# MySens-easyESP32-012.net
KiCad netlist of a schematic drawn in EAGLE
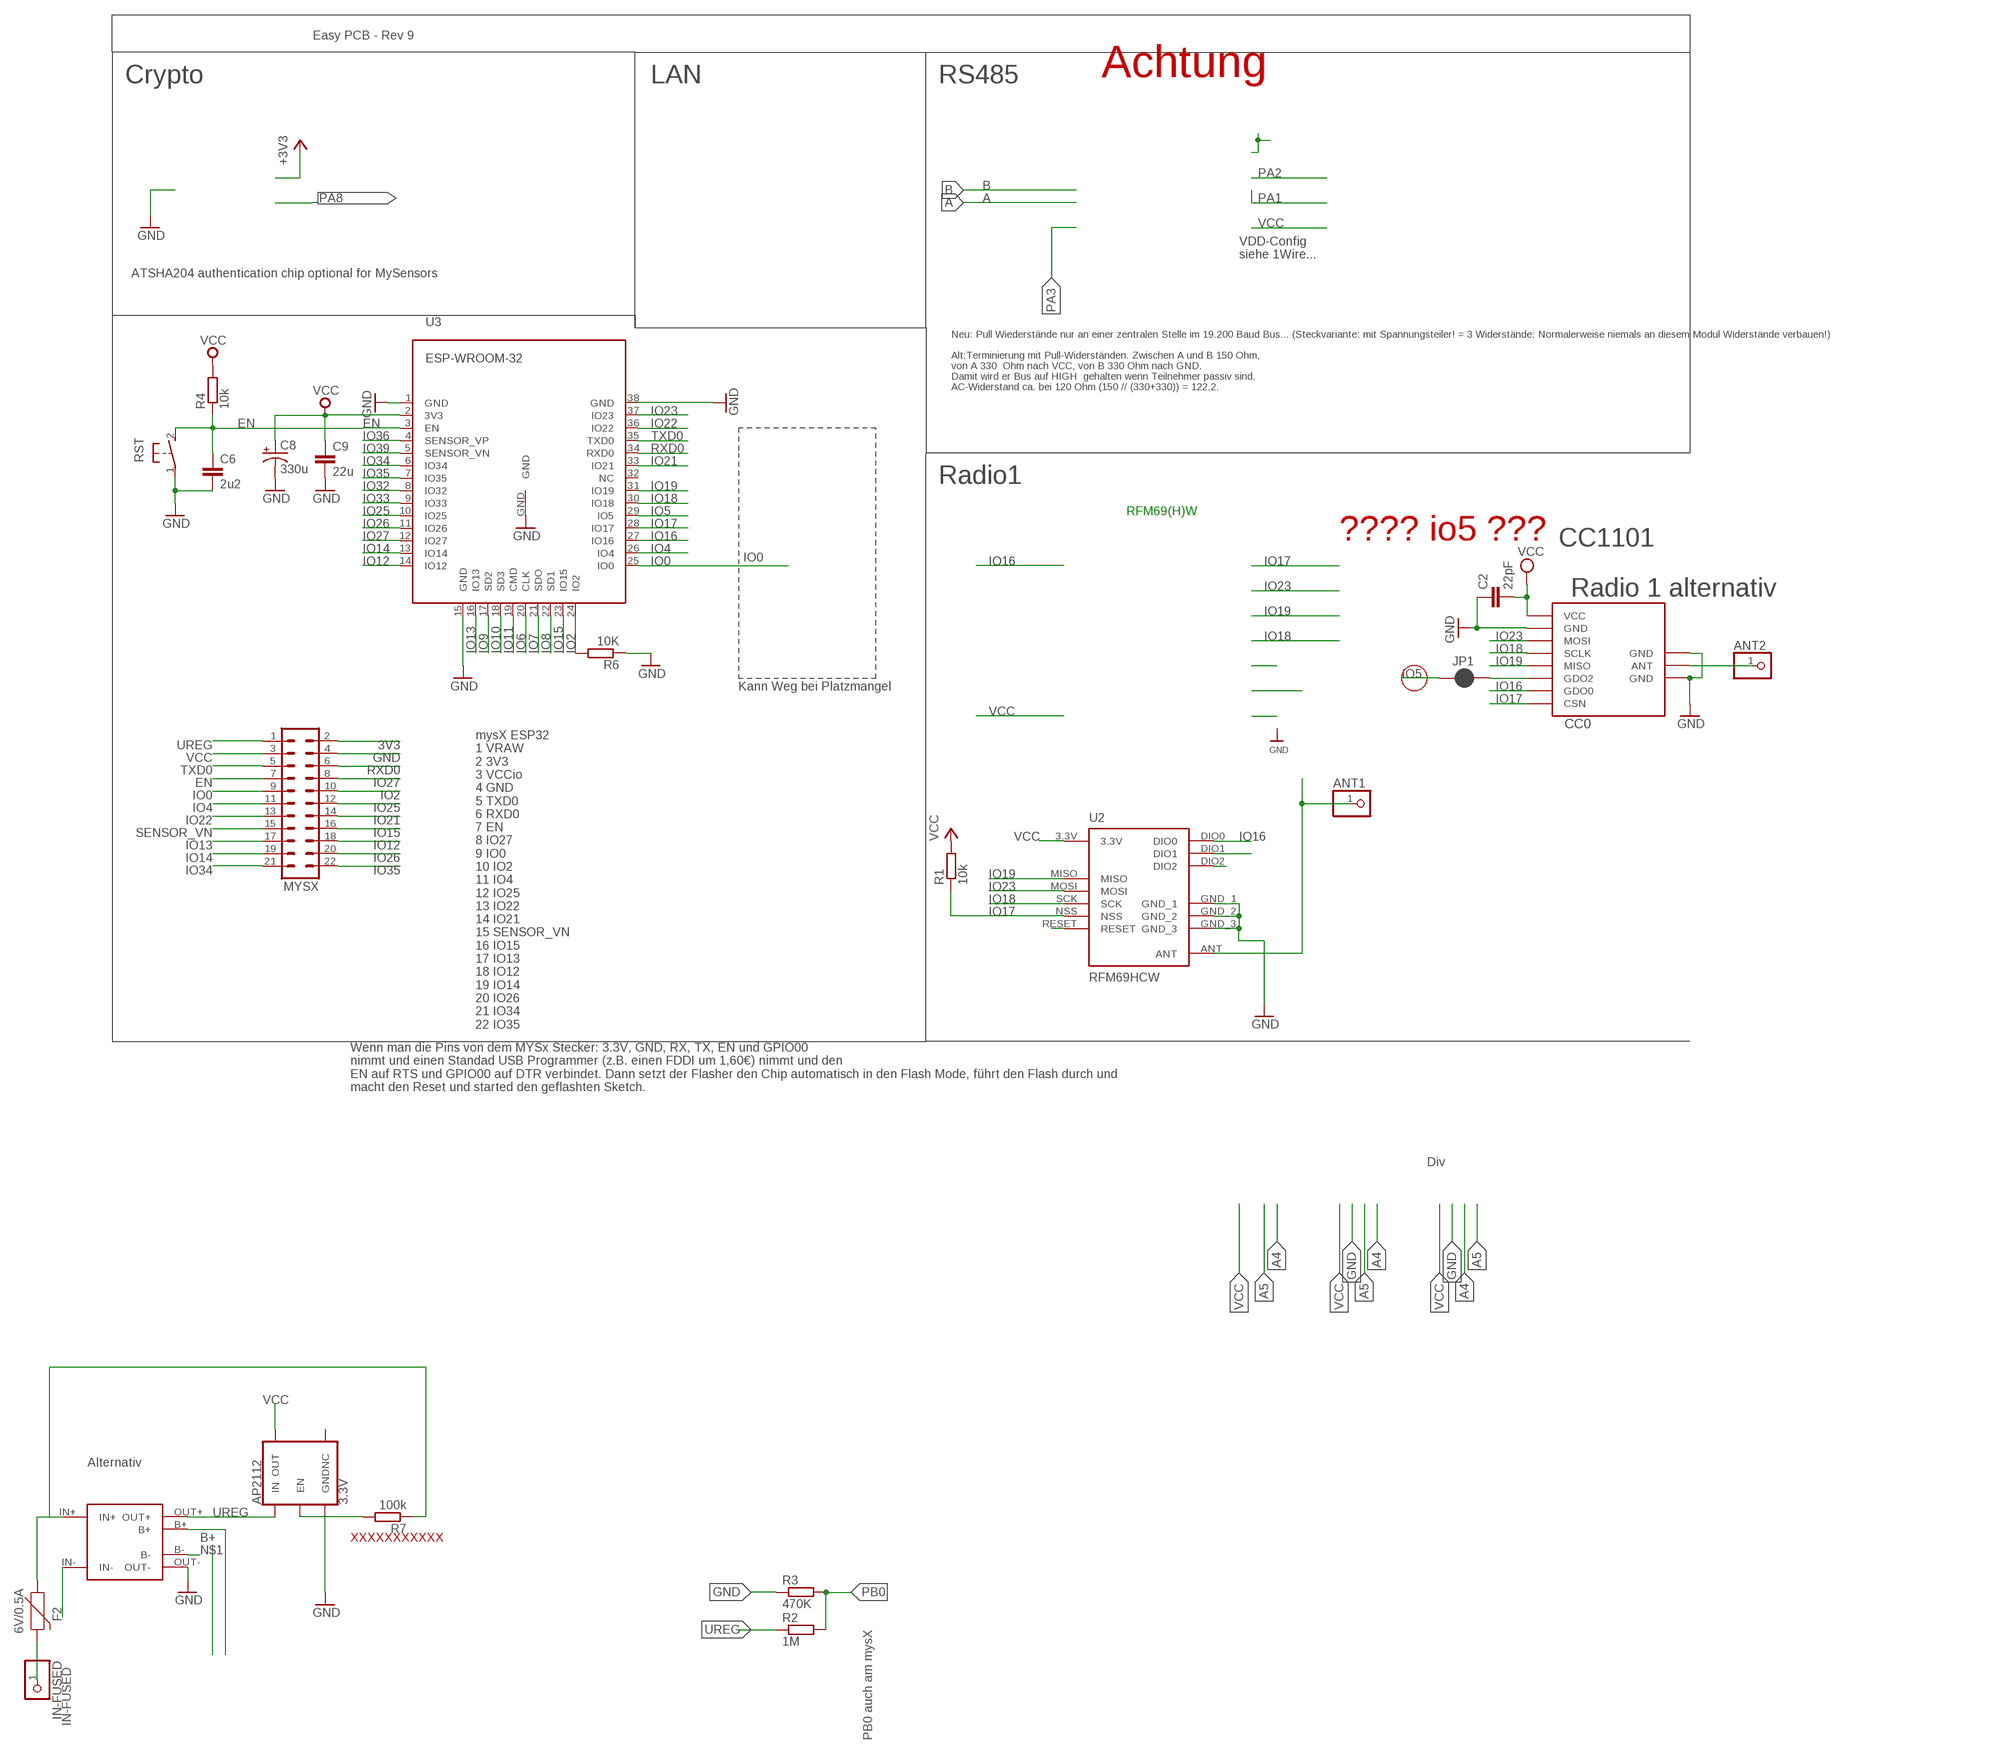
[diagram p0: schematic, sheet 1]

(export (version "E")
  (design (tool "Eeschema 10.0.6"))
  (components
    (comp (ref "ANT1")
      (value "PINHD-1X1")
      (footprint "eagle-import:1X01")
      (libsource (lib "eagle-import") (part "PINHD-1X1"))
    )
    (comp (ref "ANT2")
      (value "PINHD-1X1")
      (footprint "eagle-import:1X01")
      (libsource (lib "eagle-import") (part "PINHD-1X1"))
    )
    (comp (ref "AP2112")
      (value "3.3V")
      (footprint "eagle-import:SOT23-5")
      (libsource (lib "eagle-import") (part "V_REG_AP2112K-3.3V"))
    )
    (comp (ref "C2")
      (value "22pF")
      (footprint "eagle-import:C0805")
      (libsource (lib "eagle-import") (part "C-EUC0805"))
    )
    (comp (ref "C6")
      (value "2u2")
      (footprint "eagle-import:C0805")
      (libsource (lib "eagle-import") (part "rcl@1_C-EUC0805"))
    )
    (comp (ref "C8")
      (value "330u")
      (footprint "eagle-import:VISHAY_C")
      (libsource (lib "eagle-import") (part "CAP_POLSMD"))
    )
    (comp (ref "C9")
      (value "22u")
      (footprint "eagle-import:C0805")
      (libsource (lib "eagle-import") (part "rcl@1_C-EUC0805"))
    )
    (comp (ref "CC0")
      (value "CC1101")
      (footprint "eagle-import:CC1101_MODULE1_SMD")
      (libsource (lib "eagle-import") (part "CC1101_MODULE1SMD"))
    )
    (comp (ref "F2")
      (value "6V/0.5A")
      (footprint "eagle-import:1206")
      (libsource (lib "eagle-import") (part "PPTC_HALF-AMP"))
    )
    (comp (ref "IN-FUSED")
      (value "PINHD-1X1")
      (footprint "eagle-import:1X01")
      (libsource (lib "eagle-import") (part "PINHD-1X1"))
    )
    (comp (ref "JP1")
      (value "JUMPER-SMT_2_NC_PASTE_NO-SILK")
      (footprint "eagle-import:SMT-JUMPER_2_NC_PASTE_NO-SILK")
      (libsource (lib "eagle-import") (part "JUMPER-SMT_2_NC_PASTE_NO-SILK"))
    )
    (comp (ref "MYSX")
      (value "MA11-2")
      (footprint "eagle-import:MA11-2")
      (libsource (lib "eagle-import") (part "MA11-2"))
    )
    (comp (ref "R1")
      (value "10k")
      (footprint "eagle-import:M0805")
      (libsource (lib "eagle-import") (part "R-EU_M0805"))
    )
    (comp (ref "R2")
      (value "1M")
      (footprint "eagle-import:M0805")
      (libsource (lib "eagle-import") (part "R-EU_M0805"))
    )
    (comp (ref "R3")
      (value "470K")
      (footprint "eagle-import:M0805")
      (libsource (lib "eagle-import") (part "R-EU_M0805"))
    )
    (comp (ref "R4")
      (value "10k")
      (footprint "eagle-import:M0805")
      (libsource (lib "eagle-import") (part "rcl@1_R-EU_M0805"))
    )
    (comp (ref "R6")
      (value "10K")
      (footprint "eagle-import:M0805")
      (libsource (lib "eagle-import") (part "R-EU_M0805"))
    )
    (comp (ref "R7")
      (value "100k")
      (footprint "eagle-import:M0805")
      (libsource (lib "eagle-import") (part "R-EU_M0805"))
    )
    (comp (ref "RST")
      (value "DTSM-3")
      (footprint "eagle-import:DTSM-3")
      (libsource (lib "eagle-import") (part "DTSM-3"))
    )
    (comp (ref "TP4056")
      (value "TP4056-MODULE")
      (footprint "eagle-import:TP4056-LITHIUM-PROTECTED-MODULE")
      (libsource (lib "eagle-import") (part "TP4056-MODULE"))
    )
    (comp (ref "U2")
      (value "RFM69HCW")
      (footprint "eagle-import:RFM69HCW-XXXS2")
      (libsource (lib "eagle-import") (part "RFM69HCW"))
    )
    (comp (ref "U3")
      (value "ESP-WROOM-32")
      (footprint "eagle-import:ESP-WROOM-32")
      (libsource (lib "eagle-import") (part "ESP-WROOM-32"))
    )
  )
  (nets
    (net (code "2") (name "/3V3") (class "Default")
      (node (ref "MYSX") (pin "2") (pinfunction "2_2") (pintype "passive"))
    )
    (net (code "3") (name "/B+") (class "Default")
      (node (ref "TP4056") (pin "B+") (pinfunction "B+_B+") (pintype "power_in"))
    )
    (net (code "4") (name "/EN") (class "Default")
      (node (ref "C6") (pin "1") (pinfunction "1_1") (pintype "passive"))
      (node (ref "MYSX") (pin "7") (pinfunction "7_7") (pintype "passive"))
      (node (ref "R4") (pin "1") (pinfunction "1_1") (pintype "passive"))
      (node (ref "RST") (pin "2") (pinfunction "2_2") (pintype "passive"))
      (node (ref "U3") (pin "3") (pinfunction "EN_3") (pintype "bidirectional"))
    )
    (net (code "5") (name "/IN-FUSED") (class "Default")
      (node (ref "F2") (pin "2") (pinfunction "2_2") (pintype "bidirectional"))
      (node (ref "IN-FUSED") (pin "1") (pinfunction "1_1") (pintype "passive"))
    )
    (net (code "6") (name "/IO0") (class "Default")
      (node (ref "MYSX") (pin "9") (pinfunction "9_9") (pintype "passive"))
      (node (ref "U3") (pin "25") (pinfunction "IO0_25") (pintype "bidirectional"))
    )
    (net (code "7") (name "/IO2") (class "Default")
      (node (ref "MYSX") (pin "10") (pinfunction "10_10") (pintype "passive"))
      (node (ref "R6") (pin "2") (pinfunction "2_2") (pintype "passive"))
      (node (ref "U3") (pin "24") (pinfunction "IO2_24") (pintype "bidirectional"))
    )
    (net (code "8") (name "/IO4") (class "Default")
      (node (ref "MYSX") (pin "11") (pinfunction "11_11") (pintype "passive"))
      (node (ref "U3") (pin "26") (pinfunction "IO4_26") (pintype "bidirectional"))
    )
    (net (code "9") (name "/IO5") (class "Default")
      (node (ref "JP1") (pin "1") (pinfunction "1_1") (pintype "passive"))
      (node (ref "U3") (pin "29") (pinfunction "IO5_29") (pintype "bidirectional"))
    )
    (net (code "10") (name "/IO6") (class "Default")
      (node (ref "U3") (pin "20") (pinfunction "CLK_20") (pintype "bidirectional"))
    )
    (net (code "11") (name "/IO7") (class "Default")
      (node (ref "U3") (pin "21") (pinfunction "SDO_21") (pintype "bidirectional"))
    )
    (net (code "12") (name "/IO8") (class "Default")
      (node (ref "U3") (pin "22") (pinfunction "SD1_22") (pintype "bidirectional"))
    )
    (net (code "13") (name "/IO9") (class "Default")
      (node (ref "U3") (pin "17") (pinfunction "SD2_17") (pintype "bidirectional"))
    )
    (net (code "14") (name "/IO10") (class "Default")
      (node (ref "U3") (pin "18") (pinfunction "SD3_18") (pintype "bidirectional"))
    )
    (net (code "15") (name "/IO11") (class "Default")
      (node (ref "U3") (pin "19") (pinfunction "CMD_19") (pintype "bidirectional"))
    )
    (net (code "16") (name "/IO12") (class "Default")
      (node (ref "MYSX") (pin "18") (pinfunction "18_18") (pintype "passive"))
      (node (ref "U3") (pin "14") (pinfunction "IO12_14") (pintype "bidirectional"))
    )
    (net (code "17") (name "/IO13") (class "Default")
      (node (ref "MYSX") (pin "17") (pinfunction "17_17") (pintype "passive"))
      (node (ref "U3") (pin "16") (pinfunction "IO13_16") (pintype "bidirectional"))
    )
    (net (code "18") (name "/IO14") (class "Default")
      (node (ref "MYSX") (pin "19") (pinfunction "19_19") (pintype "passive"))
      (node (ref "U3") (pin "13") (pinfunction "IO14_13") (pintype "bidirectional"))
    )
    (net (code "19") (name "/IO15") (class "Default")
      (node (ref "MYSX") (pin "16") (pinfunction "16_16") (pintype "passive"))
      (node (ref "U3") (pin "23") (pinfunction "IO15_23") (pintype "bidirectional"))
    )
    (net (code "20") (name "/IO16") (class "Default")
      (node (ref "CC0") (pin "GDO0") (pinfunction "GDO0_GDO0") (pintype "bidirectional"))
      (node (ref "U2") (pin "DIO0") (pinfunction "DIO0_DIO0") (pintype "bidirectional"))
      (node (ref "U3") (pin "27") (pinfunction "IO16_27") (pintype "bidirectional"))
    )
    (net (code "21") (name "/IO17") (class "Default")
      (node (ref "CC0") (pin "CSN") (pinfunction "CSN_CSN") (pintype "bidirectional"))
      (node (ref "R1") (pin "1") (pinfunction "1_1") (pintype "passive"))
      (node (ref "U2") (pin "NSS") (pinfunction "NSS_NSS") (pintype "input"))
      (node (ref "U3") (pin "28") (pinfunction "IO17_28") (pintype "bidirectional"))
    )
    (net (code "22") (name "/IO18") (class "Default")
      (node (ref "CC0") (pin "SCLK") (pinfunction "SCLK_SCLK") (pintype "bidirectional"))
      (node (ref "U2") (pin "SCK") (pinfunction "SCK_SCK") (pintype "input"))
      (node (ref "U3") (pin "30") (pinfunction "IO18_30") (pintype "bidirectional"))
    )
    (net (code "23") (name "/IO19") (class "Default")
      (node (ref "CC0") (pin "MISO") (pinfunction "MISO_MISO") (pintype "bidirectional"))
      (node (ref "U2") (pin "MISO") (pinfunction "MISO_MISO") (pintype "bidirectional"))
      (node (ref "U3") (pin "31") (pinfunction "IO19_31") (pintype "bidirectional"))
    )
    (net (code "24") (name "/IO21") (class "Default")
      (node (ref "MYSX") (pin "14") (pinfunction "14_14") (pintype "passive"))
      (node (ref "U3") (pin "33") (pinfunction "IO21_33") (pintype "bidirectional"))
    )
    (net (code "25") (name "/IO22") (class "Default")
      (node (ref "MYSX") (pin "13") (pinfunction "13_13") (pintype "passive"))
      (node (ref "U3") (pin "36") (pinfunction "IO22_36") (pintype "bidirectional"))
    )
    (net (code "26") (name "/IO23") (class "Default")
      (node (ref "CC0") (pin "MOSI") (pinfunction "MOSI_MOSI") (pintype "bidirectional"))
      (node (ref "U2") (pin "MOSI") (pinfunction "MOSI_MOSI") (pintype "input"))
      (node (ref "U3") (pin "37") (pinfunction "IO23_37") (pintype "bidirectional"))
    )
    (net (code "27") (name "/IO25") (class "Default")
      (node (ref "MYSX") (pin "12") (pinfunction "12_12") (pintype "passive"))
      (node (ref "U3") (pin "10") (pinfunction "IO25_10") (pintype "bidirectional"))
    )
    (net (code "28") (name "/IO26") (class "Default")
      (node (ref "MYSX") (pin "20") (pinfunction "20_20") (pintype "passive"))
      (node (ref "U3") (pin "11") (pinfunction "IO26_11") (pintype "bidirectional"))
    )
    (net (code "29") (name "/IO27") (class "Default")
      (node (ref "MYSX") (pin "8") (pinfunction "8_8") (pintype "passive"))
      (node (ref "U3") (pin "12") (pinfunction "IO27_12") (pintype "bidirectional"))
    )
    (net (code "30") (name "/IO32") (class "Default")
      (node (ref "U3") (pin "8") (pinfunction "IO32_8") (pintype "bidirectional"))
    )
    (net (code "31") (name "/IO33") (class "Default")
      (node (ref "U3") (pin "9") (pinfunction "IO33_9") (pintype "bidirectional"))
    )
    (net (code "32") (name "/IO34") (class "Default")
      (node (ref "MYSX") (pin "21") (pinfunction "21_21") (pintype "passive"))
      (node (ref "U3") (pin "6") (pinfunction "IO34_6") (pintype "bidirectional"))
    )
    (net (code "33") (name "/IO35") (class "Default")
      (node (ref "MYSX") (pin "22") (pinfunction "22_22") (pintype "passive"))
      (node (ref "U3") (pin "7") (pinfunction "IO35_7") (pintype "bidirectional"))
    )
    (net (code "34") (name "/IO36") (class "Default")
      (node (ref "U3") (pin "4") (pinfunction "SENSOR_VP_4") (pintype "bidirectional"))
    )
    (net (code "35") (name "/IO39") (class "Default")
      (node (ref "U3") (pin "5") (pinfunction "SENSOR_VN_5") (pintype "bidirectional"))
    )
    (net (code "36") (name "/N$1") (class "Default")
      (node (ref "TP4056") (pin "B-") (pinfunction "B-_B-") (pintype "power_in"))
    )
    (net (code "40") (name "/RXD0") (class "Default")
      (node (ref "MYSX") (pin "6") (pinfunction "6_6") (pintype "passive"))
      (node (ref "U3") (pin "34") (pinfunction "RXD0_34") (pintype "bidirectional"))
    )
    (net (code "41") (name "/SENSOR_VN") (class "Default")
      (node (ref "MYSX") (pin "15") (pinfunction "15_15") (pintype "passive"))
    )
    (net (code "42") (name "/TXD0") (class "Default")
      (node (ref "MYSX") (pin "5") (pinfunction "5_5") (pintype "passive"))
      (node (ref "U3") (pin "35") (pinfunction "TXD0_35") (pintype "bidirectional"))
    )
    (net (code "47") (name "GND") (class "Default")
      (node (ref "AP2112") (pin "2") (pinfunction "GND_2") (pintype "input"))
      (node (ref "C2") (pin "1") (pinfunction "1_1") (pintype "passive"))
      (node (ref "C6") (pin "2") (pinfunction "2_2") (pintype "passive"))
      (node (ref "C8") (pin "-") (pinfunction "-_-") (pintype "passive"))
      (node (ref "C9") (pin "2") (pinfunction "2_2") (pintype "passive"))
      (node (ref "CC0") (pin "GND@0") (pinfunction "GND_GND@0") (pintype "power_in"))
      (node (ref "CC0") (pin "GND@1") (pinfunction "GND_GND@1") (pintype "power_in"))
      (node (ref "CC0") (pin "GND@2") (pinfunction "GND_GND@2") (pintype "power_in"))
      (node (ref "MYSX") (pin "4") (pinfunction "4_4") (pintype "passive"))
      (node (ref "R3") (pin "1") (pinfunction "1_1") (pintype "passive"))
      (node (ref "R6") (pin "1") (pinfunction "1_1") (pintype "passive"))
      (node (ref "RST") (pin "1") (pinfunction "1_1") (pintype "passive"))
      (node (ref "TP4056") (pin "OUT-") (pinfunction "OUT-_OUT-") (pintype "power_in"))
      (node (ref "U2") (pin "GND_1") (pinfunction "GND_1_GND_1") (pintype "power_in"))
      (node (ref "U2") (pin "GND_2") (pinfunction "GND_2_GND_2") (pintype "power_in"))
      (node (ref "U2") (pin "GND_3") (pinfunction "GND_3_GND_3") (pintype "power_in"))
      (node (ref "U3") (pin "1") (pinfunction "GND_1") (pintype "bidirectional"))
      (node (ref "U3") (pin "15") (pinfunction "GND_15") (pintype "bidirectional"))
      (node (ref "U3") (pin "38") (pinfunction "GND_38") (pintype "bidirectional"))
      (node (ref "U3") (pin "GND") (pinfunction "GND_GND") (pintype "bidirectional"))
    )
    (net (code "48") (name "Net-(ANT1-Pad1)") (class "Default")
      (node (ref "ANT1") (pin "1") (pinfunction "1_1") (pintype "passive"))
      (node (ref "U2") (pin "ANT") (pinfunction "ANT_ANT") (pintype "passive"))
    )
    (net (code "49") (name "Net-(ANT2-Pad1)") (class "Default")
      (node (ref "ANT2") (pin "1") (pinfunction "1_1") (pintype "passive"))
      (node (ref "CC0") (pin "ANT") (pinfunction "ANT_ANT") (pintype "output"))
    )
    (net (code "50") (name "Net-(AP2112-EN)") (class "Default")
      (node (ref "AP2112") (pin "3") (pinfunction "EN_3") (pintype "input"))
      (node (ref "R7") (pin "2") (pinfunction "2_2") (pintype "passive"))
    )
    (net (code "51") (name "Net-(CC0-PadGDO2)") (class "Default")
      (node (ref "CC0") (pin "GDO2") (pinfunction "GDO2_GDO2") (pintype "bidirectional"))
      (node (ref "JP1") (pin "2") (pinfunction "2_2") (pintype "passive"))
    )
    (net (code "52") (name "Net-(F2-Pad1)") (class "Default")
      (node (ref "F2") (pin "1") (pinfunction "1_1") (pintype "bidirectional"))
      (node (ref "R7") (pin "1") (pinfunction "1_1") (pintype "passive"))
      (node (ref "TP4056") (pin "IN+") (pinfunction "IN+_IN+") (pintype "power_in"))
    )
    (net (code "54") (name "PB0") (class "Default")
      (node (ref "R2") (pin "2") (pinfunction "2_2") (pintype "passive"))
      (node (ref "R3") (pin "2") (pinfunction "2_2") (pintype "passive"))
    )
    (net (code "55") (name "UREG") (class "Default")
      (node (ref "AP2112") (pin "1") (pinfunction "IN_1") (pintype "input"))
      (node (ref "MYSX") (pin "1") (pinfunction "1_1") (pintype "passive"))
      (node (ref "R2") (pin "1") (pinfunction "1_1") (pintype "passive"))
      (node (ref "TP4056") (pin "OUT+") (pinfunction "OUT+_OUT+") (pintype "power_in"))
    )
    (net (code "56") (name "VCC") (class "Default")
      (node (ref "AP2112") (pin "5") (pinfunction "OUT_5") (pintype "passive"))
      (node (ref "C2") (pin "2") (pinfunction "2_2") (pintype "passive"))
      (node (ref "C8") (pin "+") (pinfunction "+_+") (pintype "passive"))
      (node (ref "C9") (pin "1") (pinfunction "1_1") (pintype "passive"))
      (node (ref "CC0") (pin "VCC") (pinfunction "VCC_VCC") (pintype "power_in"))
      (node (ref "MYSX") (pin "3") (pinfunction "3_3") (pintype "passive"))
      (node (ref "R1") (pin "2") (pinfunction "2_2") (pintype "passive"))
      (node (ref "R4") (pin "2") (pinfunction "2_2") (pintype "passive"))
      (node (ref "U2") (pin "3.3V") (pinfunction "3.3V_3.3V") (pintype "power_in"))
      (node (ref "U3") (pin "2") (pinfunction "3V3_2") (pintype "bidirectional"))
    )
    (net (code "57") (name "unconnected-(AP2112-NC-Pad4)") (class "Default")
      (node (ref "AP2112") (pin "4") (pinfunction "NC_4") (pintype "no_connect"))
    )
    (net (code "58") (name "unconnected-(TP4056-PadIN-)") (class "Default")
      (node (ref "TP4056") (pin "IN-") (pinfunction "IN-_IN-") (pintype "power_in"))
    )
    (net (code "59") (name "unconnected-(U2-PadDIO1)") (class "Default")
      (node (ref "U2") (pin "DIO1") (pinfunction "DIO1_DIO1") (pintype "bidirectional"))
    )
    (net (code "60") (name "unconnected-(U2-PadDIO2)") (class "Default")
      (node (ref "U2") (pin "DIO2") (pinfunction "DIO2_DIO2") (pintype "bidirectional"))
    )
    (net (code "61") (name "unconnected-(U2-PadRESET)") (class "Default")
      (node (ref "U2") (pin "RESET") (pinfunction "RESET_RESET") (pintype "input"))
    )
    (net (code "62") (name "unconnected-(U3-NC-Pad32)") (class "Default")
      (node (ref "U3") (pin "32") (pinfunction "NC_32") (pintype "bidirectional"))
    )
  )
)
